# Sh_ADC-DAC_Main.net
KiCad netlist of a schematic drawn in Altium Designer
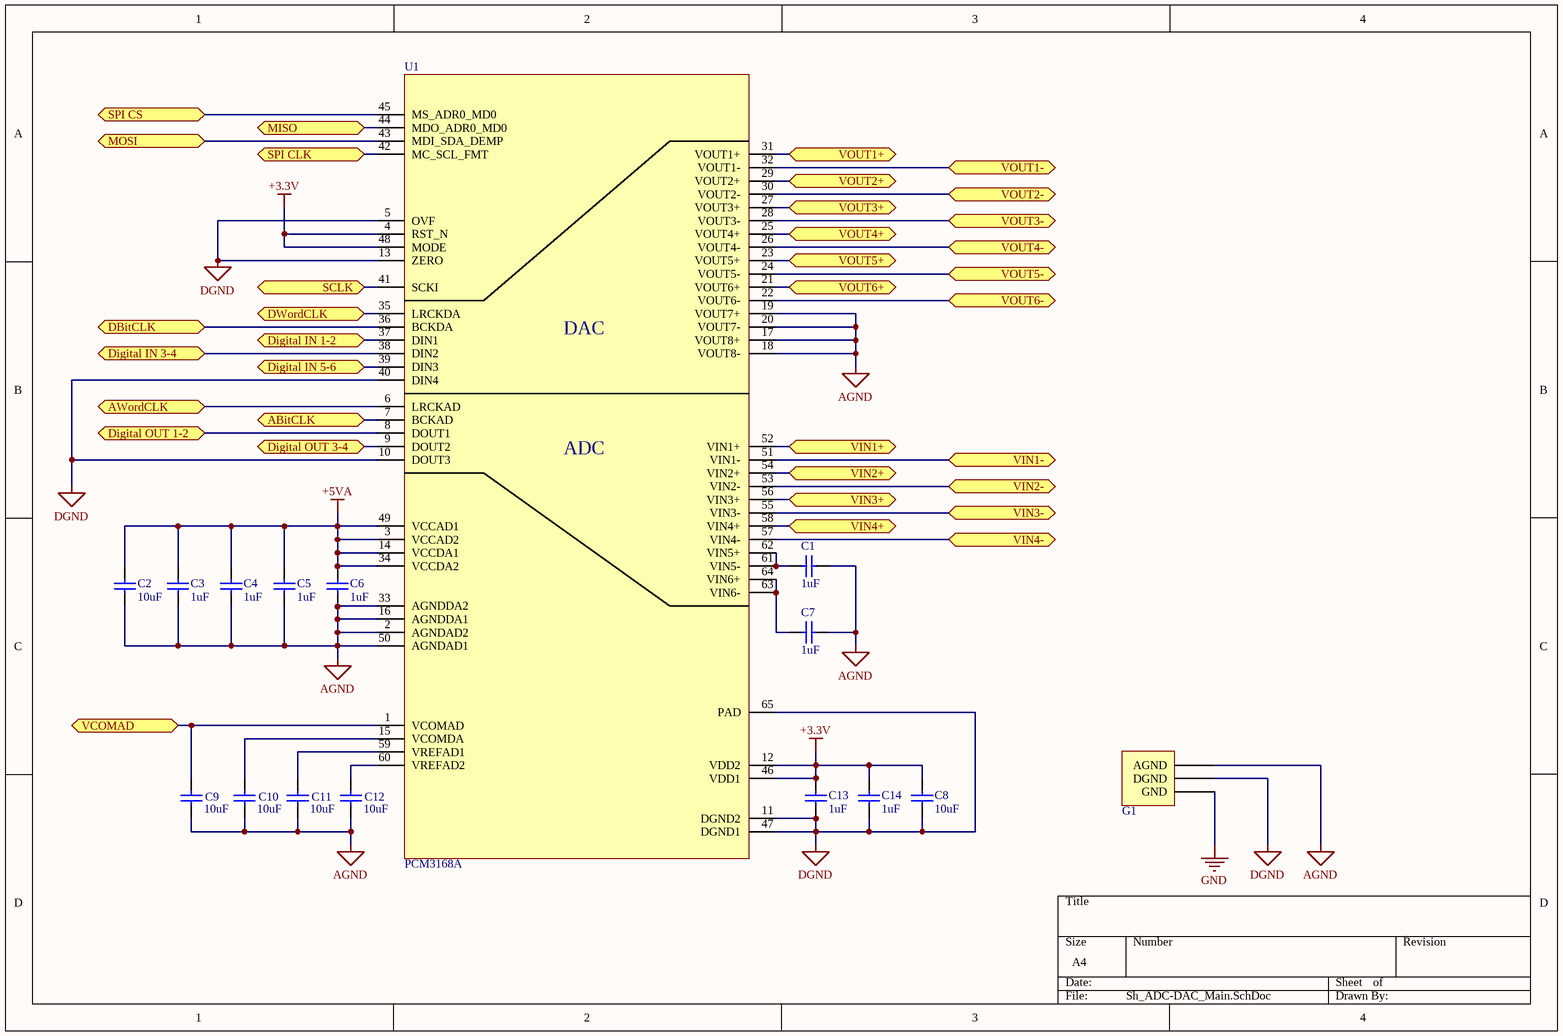
[diagram p0: Sh_ADC-DAC_Main.SchDoc]

(export (version "E")
  (design (tool "Eeschema 10.0.6"))
  (components
    (comp (ref "C1")
      (value "1uF")
      (footprint "1608[0603]")
      (description "Capacitor (Semiconductor SIM Model)")
      (fields (field (name "Comment") "Cap Semi"))
      (libsource (lib "Miscellaneous Devices") (part "Cap Semi"))
    )
    (comp (ref "C2")
      (value "10uF")
      (footprint "1608[0603]")
      (description "Capacitor (Semiconductor SIM Model)")
      (fields (field (name "Comment") "Cap Semi"))
      (libsource (lib "Miscellaneous Devices") (part "Cap Semi"))
    )
    (comp (ref "C3")
      (value "1uF")
      (footprint "1608[0603]")
      (description "Capacitor (Semiconductor SIM Model)")
      (fields (field (name "Comment") "Cap Semi"))
      (libsource (lib "Miscellaneous Devices") (part "Cap Semi"))
    )
    (comp (ref "C4")
      (value "1uF")
      (footprint "1608[0603]")
      (description "Capacitor (Semiconductor SIM Model)")
      (fields (field (name "Comment") "Cap Semi"))
      (libsource (lib "Miscellaneous Devices") (part "Cap Semi"))
    )
    (comp (ref "C5")
      (value "1uF")
      (footprint "1608[0603]")
      (description "Capacitor (Semiconductor SIM Model)")
      (fields (field (name "Comment") "Cap Semi"))
      (libsource (lib "Miscellaneous Devices") (part "Cap Semi"))
    )
    (comp (ref "C6")
      (value "1uF")
      (footprint "1608[0603]")
      (description "Capacitor (Semiconductor SIM Model)")
      (fields (field (name "Comment") "Cap Semi"))
      (libsource (lib "Miscellaneous Devices") (part "Cap Semi"))
    )
    (comp (ref "C7")
      (value "1uF")
      (footprint "1608[0603]")
      (description "Capacitor (Semiconductor SIM Model)")
      (fields (field (name "Comment") "Cap Semi"))
      (libsource (lib "Miscellaneous Devices") (part "Cap Semi"))
    )
    (comp (ref "C8")
      (value "10uF")
      (footprint "1608[0603]")
      (description "Capacitor (Semiconductor SIM Model)")
      (fields (field (name "Comment") "Cap Semi"))
      (libsource (lib "Miscellaneous Devices") (part "Cap Semi"))
    )
    (comp (ref "C9")
      (value "10uF")
      (footprint "1608[0603]")
      (description "Capacitor (Semiconductor SIM Model)")
      (fields (field (name "Comment") "Cap Semi"))
      (libsource (lib "Miscellaneous Devices") (part "Cap Semi"))
    )
    (comp (ref "C10")
      (value "10uF")
      (footprint "1608[0603]")
      (description "Capacitor (Semiconductor SIM Model)")
      (fields (field (name "Comment") "Cap Semi"))
      (libsource (lib "Miscellaneous Devices") (part "Cap Semi"))
    )
    (comp (ref "C11")
      (value "10uF")
      (footprint "1608[0603]")
      (description "Capacitor (Semiconductor SIM Model)")
      (fields (field (name "Comment") "Cap Semi"))
      (libsource (lib "Miscellaneous Devices") (part "Cap Semi"))
    )
    (comp (ref "C12")
      (value "10uF")
      (footprint "1608[0603]")
      (description "Capacitor (Semiconductor SIM Model)")
      (fields (field (name "Comment") "Cap Semi"))
      (libsource (lib "Miscellaneous Devices") (part "Cap Semi"))
    )
    (comp (ref "C13")
      (value "1uF")
      (footprint "1608[0603]")
      (description "Capacitor (Semiconductor SIM Model)")
      (fields (field (name "Comment") "Cap Semi"))
      (libsource (lib "Miscellaneous Devices") (part "Cap Semi"))
    )
    (comp (ref "C14")
      (value "1uF")
      (footprint "1608[0603]")
      (description "Capacitor (Semiconductor SIM Model)")
      (fields (field (name "Comment") "Cap Semi"))
      (libsource (lib "Miscellaneous Devices") (part "Cap Semi"))
    )
    (comp (ref "G1")
      (value "Ground Connector")
      (footprint "GND")
      (description "Ground Ultime")
      (libsource (lib "Bonjour") (part "GND"))
    )
    (comp (ref "U1")
      (value "PCM3168A")
      (footprint "PAP0064J_N")
      (description "Codec Audio, 6ADC/8DAC")
      (libsource (lib "Bonjour") (part "PCM3168APAPR"))
    )
  )
  (nets
    (net (code "1") (name "+3.3V") (class "Default")
      (node (ref "C13") (pin "2") (pinfunction "2_2") (pintype "passive"))
      (node (ref "C14") (pin "2") (pinfunction "2_2") (pintype "passive"))
      (node (ref "C8") (pin "2") (pinfunction "2_2") (pintype "passive"))
      (node (ref "U1") (pin "12") (pinfunction "VDD2_12") (pintype "passive"))
      (node (ref "U1") (pin "4") (pinfunction "RST_N_4") (pintype "passive"))
      (node (ref "U1") (pin "46") (pinfunction "VDD1_46") (pintype "passive"))
      (node (ref "U1") (pin "48") (pinfunction "MODE_48") (pintype "passive"))
    )
    (net (code "2") (name "+5VA") (class "Default")
      (node (ref "C2") (pin "2") (pinfunction "2_2") (pintype "passive"))
      (node (ref "C3") (pin "2") (pinfunction "2_2") (pintype "passive"))
      (node (ref "C4") (pin "2") (pinfunction "2_2") (pintype "passive"))
      (node (ref "C5") (pin "2") (pinfunction "2_2") (pintype "passive"))
      (node (ref "C6") (pin "2") (pinfunction "2_2") (pintype "passive"))
      (node (ref "U1") (pin "14") (pinfunction "VCCDA1_14") (pintype "passive"))
      (node (ref "U1") (pin "3") (pinfunction "VCCAD2_3") (pintype "passive"))
      (node (ref "U1") (pin "34") (pinfunction "VCCDA2_34") (pintype "passive"))
      (node (ref "U1") (pin "49") (pinfunction "VCCAD1_49") (pintype "passive"))
    )
    (net (code "3") (name "/ABitCLK") (class "Default")
      (node (ref "U1") (pin "7") (pinfunction "BCKAD_7") (pintype "passive"))
    )
    (net (code "4") (name "/AWordCLK") (class "Default")
      (node (ref "U1") (pin "6") (pinfunction "LRCKAD_6") (pintype "passive"))
    )
    (net (code "5") (name "/DBitCLK") (class "Default")
      (node (ref "U1") (pin "36") (pinfunction "BCKDA_36") (pintype "passive"))
    )
    (net (code "6") (name "/DWordCLK") (class "Default")
      (node (ref "U1") (pin "35") (pinfunction "LRCKDA_35") (pintype "passive"))
    )
    (net (code "7") (name "/Digital IN 1-2") (class "Default")
      (node (ref "U1") (pin "37") (pinfunction "DIN1_37") (pintype "passive"))
    )
    (net (code "8") (name "/Digital IN 3-4") (class "Default")
      (node (ref "U1") (pin "38") (pinfunction "DIN2_38") (pintype "passive"))
    )
    (net (code "9") (name "/Digital IN 5-6") (class "Default")
      (node (ref "U1") (pin "39") (pinfunction "DIN3_39") (pintype "passive"))
    )
    (net (code "10") (name "/Digital OUT 1-2") (class "Default")
      (node (ref "U1") (pin "8") (pinfunction "DOUT1_8") (pintype "passive"))
    )
    (net (code "11") (name "/Digital OUT 3-4") (class "Default")
      (node (ref "U1") (pin "9") (pinfunction "DOUT2_9") (pintype "passive"))
    )
    (net (code "12") (name "/MISO") (class "Default")
      (node (ref "U1") (pin "44") (pinfunction "MDO_ADR0_MD0_44") (pintype "passive"))
    )
    (net (code "13") (name "/MOSI") (class "Default")
      (node (ref "U1") (pin "43") (pinfunction "MDI_SDA_DEMP_43") (pintype "passive"))
    )
    (net (code "14") (name "/SCLK") (class "Default")
      (node (ref "U1") (pin "41") (pinfunction "SCKI_41") (pintype "passive"))
    )
    (net (code "15") (name "/SPI CLK") (class "Default")
      (node (ref "U1") (pin "42") (pinfunction "MC_SCL_FMT_42") (pintype "passive"))
    )
    (net (code "16") (name "/SPI CS") (class "Default")
      (node (ref "U1") (pin "45") (pinfunction "MS_ADR0_MD0_45") (pintype "passive"))
    )
    (net (code "17") (name "/VCOMAD") (class "Default")
      (node (ref "C9") (pin "2") (pinfunction "2_2") (pintype "passive"))
      (node (ref "U1") (pin "1") (pinfunction "VCOMAD_1") (pintype "passive"))
    )
    (net (code "18") (name "/VIN1+") (class "Default")
      (node (ref "U1") (pin "52") (pinfunction "VIN1+_52") (pintype "passive"))
    )
    (net (code "19") (name "/VIN1-") (class "Default")
      (node (ref "U1") (pin "51") (pinfunction "VIN1-_51") (pintype "passive"))
    )
    (net (code "20") (name "/VIN2+") (class "Default")
      (node (ref "U1") (pin "54") (pinfunction "VIN2+_54") (pintype "passive"))
    )
    (net (code "21") (name "/VIN2-") (class "Default")
      (node (ref "U1") (pin "53") (pinfunction "VIN2-_53") (pintype "passive"))
    )
    (net (code "22") (name "/VIN3+") (class "Default")
      (node (ref "U1") (pin "56") (pinfunction "VIN3+_56") (pintype "passive"))
    )
    (net (code "23") (name "/VIN3-") (class "Default")
      (node (ref "U1") (pin "55") (pinfunction "VIN3-_55") (pintype "passive"))
    )
    (net (code "24") (name "/VIN4+") (class "Default")
      (node (ref "U1") (pin "58") (pinfunction "VIN4+_58") (pintype "passive"))
    )
    (net (code "25") (name "/VIN4-") (class "Default")
      (node (ref "U1") (pin "57") (pinfunction "VIN4-_57") (pintype "passive"))
    )
    (net (code "26") (name "/VOUT1+") (class "Default")
      (node (ref "U1") (pin "31") (pinfunction "VOUT1+_31") (pintype "passive"))
    )
    (net (code "27") (name "/VOUT1-") (class "Default")
      (node (ref "U1") (pin "32") (pinfunction "VOUT1-_32") (pintype "passive"))
    )
    (net (code "28") (name "/VOUT2+") (class "Default")
      (node (ref "U1") (pin "29") (pinfunction "VOUT2+_29") (pintype "passive"))
    )
    (net (code "29") (name "/VOUT2-") (class "Default")
      (node (ref "U1") (pin "30") (pinfunction "VOUT2-_30") (pintype "passive"))
    )
    (net (code "30") (name "/VOUT3+") (class "Default")
      (node (ref "U1") (pin "27") (pinfunction "VOUT3+_27") (pintype "passive"))
    )
    (net (code "31") (name "/VOUT3-") (class "Default")
      (node (ref "U1") (pin "28") (pinfunction "VOUT3-_28") (pintype "passive"))
    )
    (net (code "32") (name "/VOUT4+") (class "Default")
      (node (ref "U1") (pin "25") (pinfunction "VOUT4+_25") (pintype "passive"))
    )
    (net (code "33") (name "/VOUT4-") (class "Default")
      (node (ref "U1") (pin "26") (pinfunction "VOUT4-_26") (pintype "passive"))
    )
    (net (code "34") (name "/VOUT5+") (class "Default")
      (node (ref "U1") (pin "23") (pinfunction "VOUT5+_23") (pintype "passive"))
    )
    (net (code "35") (name "/VOUT5-") (class "Default")
      (node (ref "U1") (pin "24") (pinfunction "VOUT5-_24") (pintype "passive"))
    )
    (net (code "36") (name "/VOUT6+") (class "Default")
      (node (ref "U1") (pin "21") (pinfunction "VOUT6+_21") (pintype "passive"))
    )
    (net (code "37") (name "/VOUT6-") (class "Default")
      (node (ref "U1") (pin "22") (pinfunction "VOUT6-_22") (pintype "passive"))
    )
    (net (code "38") (name "AGND") (class "Default")
      (node (ref "C1") (pin "1") (pinfunction "1_1") (pintype "passive"))
      (node (ref "C10") (pin "1") (pinfunction "1_1") (pintype "passive"))
      (node (ref "C11") (pin "1") (pinfunction "1_1") (pintype "passive"))
      (node (ref "C12") (pin "1") (pinfunction "1_1") (pintype "passive"))
      (node (ref "C2") (pin "1") (pinfunction "1_1") (pintype "passive"))
      (node (ref "C3") (pin "1") (pinfunction "1_1") (pintype "passive"))
      (node (ref "C4") (pin "1") (pinfunction "1_1") (pintype "passive"))
      (node (ref "C5") (pin "1") (pinfunction "1_1") (pintype "passive"))
      (node (ref "C6") (pin "1") (pinfunction "1_1") (pintype "passive"))
      (node (ref "C7") (pin "1") (pinfunction "1_1") (pintype "passive"))
      (node (ref "C9") (pin "1") (pinfunction "1_1") (pintype "passive"))
      (node (ref "G1") (pin "1") (pinfunction "AGND_1") (pintype "passive"))
      (node (ref "U1") (pin "16") (pinfunction "AGNDDA1_16") (pintype "passive"))
      (node (ref "U1") (pin "17") (pinfunction "VOUT8+_17") (pintype "passive"))
      (node (ref "U1") (pin "18") (pinfunction "VOUT8-_18") (pintype "passive"))
      (node (ref "U1") (pin "19") (pinfunction "VOUT7+_19") (pintype "passive"))
      (node (ref "U1") (pin "2") (pinfunction "AGNDAD2_2") (pintype "passive"))
      (node (ref "U1") (pin "20") (pinfunction "VOUT7-_20") (pintype "passive"))
      (node (ref "U1") (pin "33") (pinfunction "AGNDDA2_33") (pintype "passive"))
      (node (ref "U1") (pin "50") (pinfunction "AGNDAD1_50") (pintype "passive"))
    )
    (net (code "39") (name "DGND") (class "Default")
      (node (ref "C13") (pin "1") (pinfunction "1_1") (pintype "passive"))
      (node (ref "C14") (pin "1") (pinfunction "1_1") (pintype "passive"))
      (node (ref "C8") (pin "1") (pinfunction "1_1") (pintype "passive"))
      (node (ref "G1") (pin "2") (pinfunction "DGND_2") (pintype "passive"))
      (node (ref "U1") (pin "10") (pinfunction "DOUT3_10") (pintype "passive"))
      (node (ref "U1") (pin "11") (pinfunction "DGND2_11") (pintype "passive"))
      (node (ref "U1") (pin "13") (pinfunction "ZERO_13") (pintype "passive"))
      (node (ref "U1") (pin "40") (pinfunction "DIN4_40") (pintype "passive"))
      (node (ref "U1") (pin "47") (pinfunction "DGND1_47") (pintype "passive"))
      (node (ref "U1") (pin "5") (pinfunction "OVF_5") (pintype "passive"))
      (node (ref "U1") (pin "65") (pinfunction "PAD_65") (pintype "passive"))
    )
    (net (code "40") (name "GND") (class "Default")
      (node (ref "G1") (pin "3") (pinfunction "GND_3") (pintype "passive"))
    )
    (net (code "41") (name "Net-(U1-VCOMDA)") (class "Default")
      (node (ref "C10") (pin "2") (pinfunction "2_2") (pintype "passive"))
      (node (ref "U1") (pin "15") (pinfunction "VCOMDA_15") (pintype "passive"))
    )
    (net (code "42") (name "Net-(U1-VIN5+)") (class "Default")
      (node (ref "C1") (pin "2") (pinfunction "2_2") (pintype "passive"))
      (node (ref "U1") (pin "61") (pinfunction "VIN5-_61") (pintype "passive"))
      (node (ref "U1") (pin "62") (pinfunction "VIN5+_62") (pintype "passive"))
    )
    (net (code "43") (name "Net-(U1-VIN6+)") (class "Default")
      (node (ref "C7") (pin "2") (pinfunction "2_2") (pintype "passive"))
      (node (ref "U1") (pin "63") (pinfunction "VIN6-_63") (pintype "passive"))
      (node (ref "U1") (pin "64") (pinfunction "VIN6+_64") (pintype "passive"))
    )
    (net (code "44") (name "Net-(U1-VREFAD1)") (class "Default")
      (node (ref "C11") (pin "2") (pinfunction "2_2") (pintype "passive"))
      (node (ref "U1") (pin "59") (pinfunction "VREFAD1_59") (pintype "passive"))
    )
    (net (code "45") (name "Net-(U1-VREFAD2)") (class "Default")
      (node (ref "C12") (pin "2") (pinfunction "2_2") (pintype "passive"))
      (node (ref "U1") (pin "60") (pinfunction "VREFAD2_60") (pintype "passive"))
    )
  )
)
